# FPGA_Bank_0_CFG.net
KiCad netlist of a schematic drawn in Altium Designer
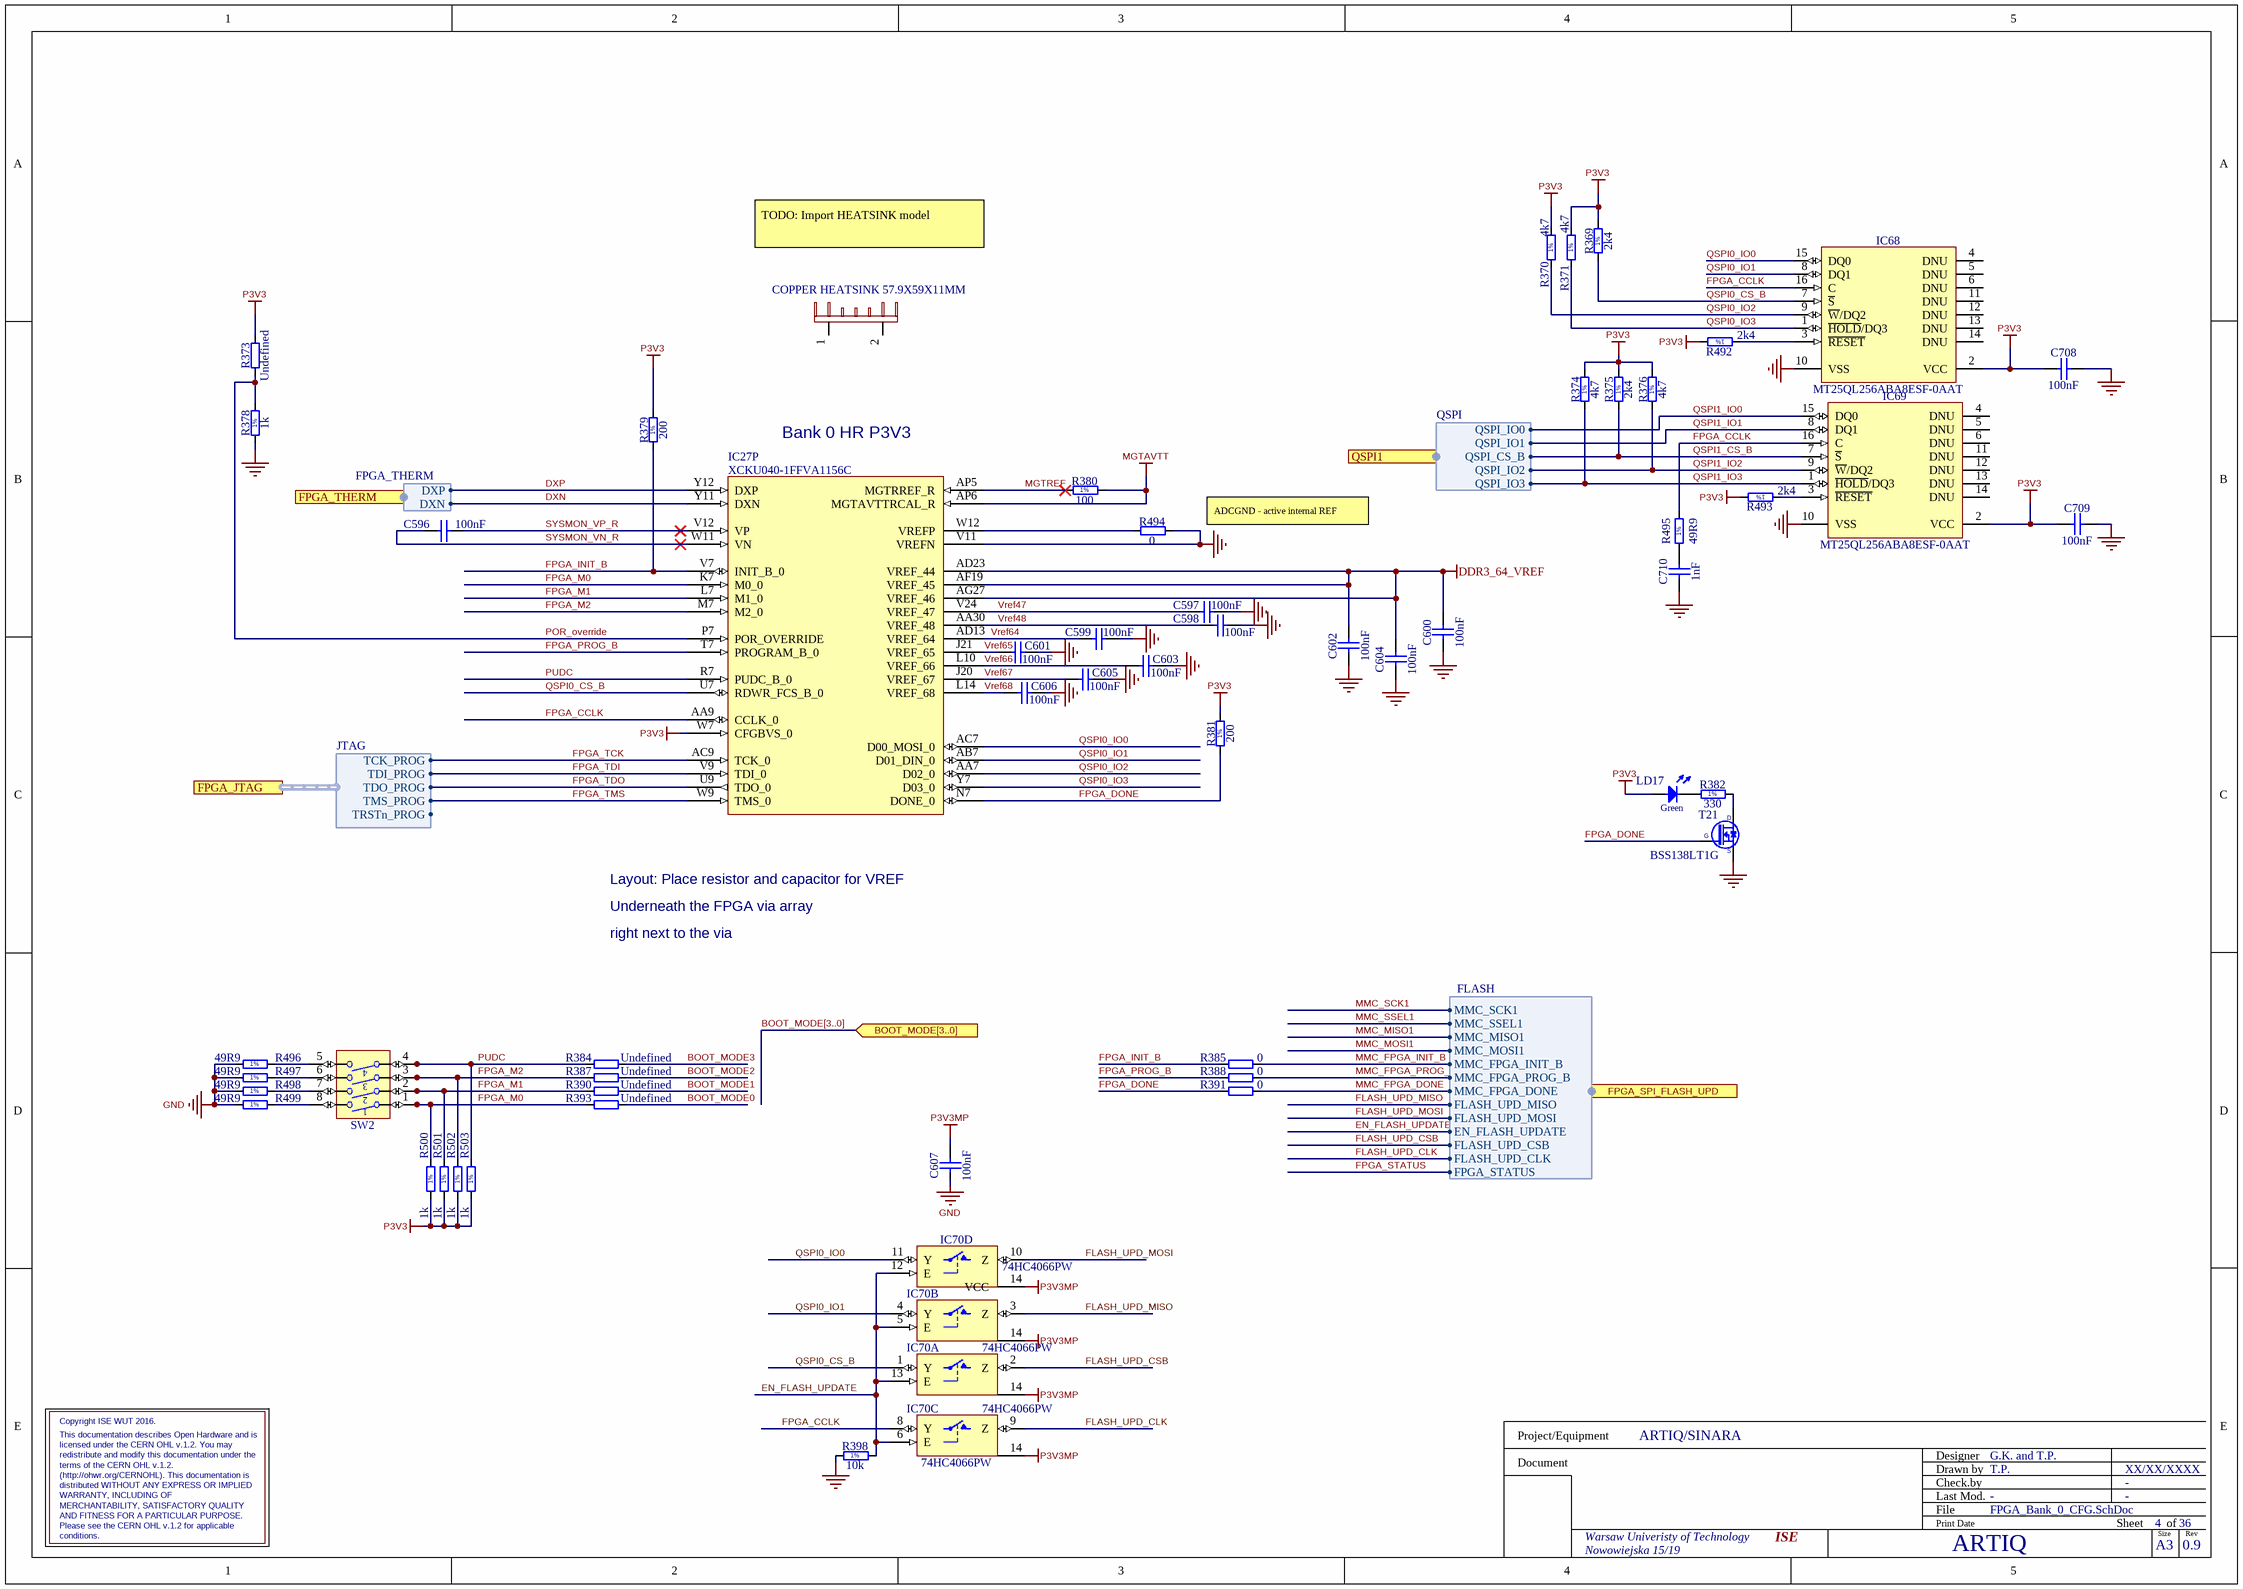
[diagram p0: FPGA_Bank_0_CFG.SchDoc]

(export (version "E")
  (design (tool "Eeschema 10.0.6"))
  (components
    (comp (ref "C596")
      (value "100nF")
      (footprint "CAPC0603X33N")
      (description "Non-polarised capacitor")
      (fields
        (field (name "MANUFACTURER PART NUMBER") "CC0201_100NF_6.3V_10%_X5R")
        (field (name "MANUFACTURER") "GENERIC")
        (field (name "AUTHOR") "CERN DEM JLC")
      )
      (libsource (lib "Capacitors") (part "Capacitor - non polarized"))
    )
    (comp (ref "C597")
      (value "100nF")
      (footprint "CAPC0603X33N")
      (description "Non-polarised capacitor")
      (fields
        (field (name "MANUFACTURER PART NUMBER") "CC0201_100NF_6.3V_10%_X5R")
        (field (name "MANUFACTURER") "GENERIC")
        (field (name "AUTHOR") "CERN DEM JLC")
      )
      (libsource (lib "Capacitors") (part "Capacitor - non polarized"))
    )
    (comp (ref "C598")
      (value "100nF")
      (footprint "CAPC0603X33N")
      (description "Non-polarised capacitor")
      (fields
        (field (name "MANUFACTURER PART NUMBER") "CC0201_100NF_6.3V_10%_X5R")
        (field (name "MANUFACTURER") "GENERIC")
        (field (name "AUTHOR") "CERN DEM JLC")
      )
      (libsource (lib "Capacitors") (part "Capacitor - non polarized"))
    )
    (comp (ref "C599")
      (value "100nF")
      (footprint "CAPC0603X33N")
      (description "Non-polarised capacitor")
      (fields
        (field (name "MANUFACTURER PART NUMBER") "CC0201_100NF_6.3V_10%_X5R")
        (field (name "MANUFACTURER") "GENERIC")
        (field (name "AUTHOR") "CERN DEM JLC")
      )
      (libsource (lib "Capacitors") (part "Capacitor - non polarized"))
    )
    (comp (ref "C600")
      (value "100nF")
      (footprint "CAPC0603X33N")
      (description "Non-polarised capacitor")
      (fields
        (field (name "MANUFACTURER PART NUMBER") "CC0201_100NF_6.3V_10%_X5R")
        (field (name "MANUFACTURER") "GENERIC")
        (field (name "AUTHOR") "CERN DEM JLC")
      )
      (libsource (lib "Capacitors") (part "Capacitor - non polarized"))
    )
    (comp (ref "C601")
      (value "100nF")
      (footprint "CAPC0603X33N")
      (description "Non-polarised capacitor")
      (fields
        (field (name "MANUFACTURER PART NUMBER") "CC0201_100NF_6.3V_10%_X5R")
        (field (name "MANUFACTURER") "GENERIC")
        (field (name "AUTHOR") "CERN DEM JLC")
      )
      (libsource (lib "Capacitors") (part "Capacitor - non polarized"))
    )
    (comp (ref "C602")
      (value "100nF")
      (footprint "CAPC0603X33N")
      (description "Non-polarised capacitor")
      (fields
        (field (name "MANUFACTURER PART NUMBER") "CC0201_100NF_6.3V_10%_X5R")
        (field (name "MANUFACTURER") "GENERIC")
        (field (name "AUTHOR") "CERN DEM JLC")
      )
      (libsource (lib "Capacitors") (part "Capacitor - non polarized"))
    )
    (comp (ref "C603")
      (value "100nF")
      (footprint "CAPC0603X33N")
      (description "Non-polarised capacitor")
      (fields
        (field (name "MANUFACTURER PART NUMBER") "CC0201_100NF_6.3V_10%_X5R")
        (field (name "MANUFACTURER") "GENERIC")
        (field (name "AUTHOR") "CERN DEM JLC")
      )
      (libsource (lib "Capacitors") (part "Capacitor - non polarized"))
    )
    (comp (ref "C604")
      (value "100nF")
      (footprint "CAPC0603X33N")
      (description "Non-polarised capacitor")
      (fields
        (field (name "MANUFACTURER PART NUMBER") "CC0201_100NF_6.3V_10%_X5R")
        (field (name "MANUFACTURER") "GENERIC")
        (field (name "AUTHOR") "CERN DEM JLC")
      )
      (libsource (lib "Capacitors") (part "Capacitor - non polarized"))
    )
    (comp (ref "C605")
      (value "100nF")
      (footprint "CAPC0603X33N")
      (description "Non-polarised capacitor")
      (fields
        (field (name "MANUFACTURER PART NUMBER") "CC0201_100NF_6.3V_10%_X5R")
        (field (name "MANUFACTURER") "GENERIC")
        (field (name "AUTHOR") "CERN DEM JLC")
      )
      (libsource (lib "Capacitors") (part "Capacitor - non polarized"))
    )
    (comp (ref "C606")
      (value "100nF")
      (footprint "CAPC0603X33N")
      (description "Non-polarised capacitor")
      (fields
        (field (name "MANUFACTURER PART NUMBER") "CC0201_100NF_6.3V_10%_X5R")
        (field (name "MANUFACTURER") "GENERIC")
        (field (name "AUTHOR") "CERN DEM JLC")
      )
      (libsource (lib "Capacitors") (part "Capacitor - non polarized"))
    )
    (comp (ref "C607")
      (value "100nF")
      (footprint "CAPC0603X33N")
      (description "Non-polarised capacitor")
      (fields
        (field (name "MANUFACTURER PART NUMBER") "CC0201_100NF_6.3V_10%_X5R")
        (field (name "MANUFACTURER") "GENERIC")
        (field (name "AUTHOR") "CERN DEM JLC")
      )
      (libsource (lib "Capacitors") (part "Capacitor - non polarized"))
    )
    (comp (ref "C708")
      (value "100nF")
      (footprint "CAPC0603X33N")
      (description "Non-polarised capacitor")
      (fields
        (field (name "MANUFACTURER PART NUMBER") "CC0201_100NF_6.3V_10%_X5R")
        (field (name "MANUFACTURER") "GENERIC")
        (field (name "AUTHOR") "CERN DEM JLC")
      )
      (libsource (lib "Capacitors") (part "Capacitor - non polarized"))
    )
    (comp (ref "C709")
      (value "100nF")
      (footprint "CAPC0603X33N")
      (description "Non-polarised capacitor")
      (fields
        (field (name "MANUFACTURER PART NUMBER") "CC0201_100NF_6.3V_10%_X5R")
        (field (name "MANUFACTURER") "GENERIC")
        (field (name "AUTHOR") "CERN DEM JLC")
      )
      (libsource (lib "Capacitors") (part "Capacitor - non polarized"))
    )
    (comp (ref "C710")
      (value "1nF")
      (footprint "CAPC1005X55N")
      (description "Non-polarised capacitor")
      (fields
        (field (name "MANUFACTURER PART NUMBER") "CC0402_1NF_50V_10%_X7R")
        (field (name "MANUFACTURER") "GENERIC")
        (field (name "AUTHOR") "CERN DEM JLC")
      )
      (libsource (lib "Capacitors") (part "Capacitor - non polarized"))
    )
    (comp (ref "HS1")
      (value "1.9K/W")
      (fields
        (field (name "MANUFACTURER PART NUMBER") "342947")
        (field (name "MANUFACTURER") "Aavid Thermalloy")
        (field (name "PART DESCRIPTION") "COPPER HEATSINK 57.9X59X11MM")
        (field (name "PART NUMBER") "HSINK_AAVID_342947")
      )
      (libsource (lib "altium-import") (part "root_0__Eletro-mechanical.DbLib"))
    )
    (comp (ref "IC27")
      (value "XCKU040-1FFVA1156C")
      (footprint "BGA1156C100P34X34_3500X3500X350")
      (description "Kintex UltraScale FPGA, 520 I/O, 530K Cells, 1156-Ball BGA, Speed Grade 1, Commercial Grade")
      (fields (field (name "MANUFACTURER") "XILINX") (field (name "AUTHOR") "CERN DEM CA"))
      (libsource (lib "ICs And Semiconductors") (part "XCKU040-1FFVA1156C"))
    )
    (comp (ref "IC68")
      (value "MT25QL256ABA8ESF-0AAT")
      (footprint "SOIC127P1030X265-16N")
      (description "256Mbit (32MB), 2.7V-3.6V, Multiple I/O Serial NOR Flash Memory,with Reset# & Hold#")
      (fields (field (name "MANUFACTURER") "MICRON TECHNOLOGY") (field (name "AUTHOR") "CERN DEM JLC"))
      (libsource (lib "ICs And Semiconductors") (part "MT25QL256ABA8ESF"))
    )
    (comp (ref "IC69")
      (value "MT25QL256ABA8ESF-0AAT")
      (footprint "SOIC127P1030X265-16N")
      (description "256Mbit (32MB), 2.7V-3.6V, Multiple I/O Serial NOR Flash Memory,with Reset# & Hold#")
      (fields (field (name "MANUFACTURER") "MICRON TECHNOLOGY") (field (name "AUTHOR") "CERN DEM JLC"))
      (libsource (lib "ICs And Semiconductors") (part "MT25QL256ABA8ESF"))
    )
    (comp (ref "IC70")
      (value "74HC4066PW")
      (footprint "SOP65P640X110-14N")
      (fields (field (name "MANUFACTURER") "NXP SEMICONDUCTORS") (field (name "AUTHOR") "CERN DEM JLC"))
      (libsource (lib "ICs And Semiconductors") (part "4066"))
    )
    (comp (ref "LD17")
      (value "Green")
      (footprint "LED_AVAGO_HSME-C120")
      (description "LED Green 1C 2A")
      (fields
        (field (name "MANUFACTURER PART NUMBER") "HSME-C120")
        (field (name "MANUFACTURER") "AVAGO TECHNOLOGIES")
        (field (name "AUTHOR") "CERN DEM JMW")
      )
      (libsource (lib "ICs And Semiconductors") (part "LED Green 1C 2A"))
    )
    (comp (ref "R369")
      (value "2k4")
      (footprint "RESC1005X40N")
      (description "Resistor - 1%")
      (fields
        (field (name "MANUFACTURER PART NUMBER") "R0402_2K4_1%_0.0625W_100PPM")
        (field (name "MANUFACTURER") "GENERIC")
        (field (name "AUTHOR") "CERN DEM JLC")
      )
      (libsource (lib "Resistors") (part "Resistor - 1%"))
    )
    (comp (ref "R370")
      (value "4k7")
      (footprint "RESC1005X40N")
      (description "Resistor - 1%")
      (fields
        (field (name "MANUFACTURER PART NUMBER") "R0402_4K7_1%_0.0625W_100PPM")
        (field (name "MANUFACTURER") "GENERIC")
        (field (name "AUTHOR") "CERN DEM JLC")
      )
      (libsource (lib "Resistors") (part "Resistor - 1%"))
    )
    (comp (ref "R371")
      (value "4k7")
      (footprint "RESC1005X40N")
      (description "Resistor - 1%")
      (fields
        (field (name "MANUFACTURER PART NUMBER") "R0402_4K7_1%_0.0625W_100PPM")
        (field (name "MANUFACTURER") "GENERIC")
        (field (name "AUTHOR") "CERN DEM JLC")
      )
      (libsource (lib "Resistors") (part "Resistor - 1%"))
    )
    (comp (ref "R373")
      (value "Undefined")
      (footprint "RESC1005X40N")
      (description "Resistor")
      (fields
        (field (name "MANUFACTURER PART NUMBER") "R0402_NO-VALUE")
        (field (name "AUTHOR") "CERN DEM JLC")
      )
      (libsource (lib "Resistors") (part "Resistor"))
    )
    (comp (ref "R374")
      (value "4k7")
      (footprint "RESC1005X40N")
      (description "Resistor - 1%")
      (fields
        (field (name "MANUFACTURER PART NUMBER") "R0402_4K7_1%_0.0625W_100PPM")
        (field (name "MANUFACTURER") "GENERIC")
        (field (name "AUTHOR") "CERN DEM JLC")
      )
      (libsource (lib "Resistors") (part "Resistor - 1%"))
    )
    (comp (ref "R375")
      (value "2k4")
      (footprint "RESC1005X40N")
      (description "Resistor - 1%")
      (fields
        (field (name "MANUFACTURER PART NUMBER") "R0402_2K4_1%_0.0625W_100PPM")
        (field (name "MANUFACTURER") "GENERIC")
        (field (name "AUTHOR") "CERN DEM JLC")
      )
      (libsource (lib "Resistors") (part "Resistor - 1%"))
    )
    (comp (ref "R376")
      (value "4k7")
      (footprint "RESC1005X40N")
      (description "Resistor - 1%")
      (fields
        (field (name "MANUFACTURER PART NUMBER") "R0402_4K7_1%_0.0625W_100PPM")
        (field (name "MANUFACTURER") "GENERIC")
        (field (name "AUTHOR") "CERN DEM JLC")
      )
      (libsource (lib "Resistors") (part "Resistor - 1%"))
    )
    (comp (ref "R378")
      (value "1k")
      (footprint "RESC1005X40N")
      (description "Resistor - 1%")
      (fields
        (field (name "MANUFACTURER PART NUMBER") "R0402_1K_1%_0.0625W_100PPM")
        (field (name "MANUFACTURER") "GENERIC")
        (field (name "AUTHOR") "CERN DEM JLC")
      )
      (libsource (lib "Resistors") (part "Resistor - 1%"))
    )
    (comp (ref "R379")
      (value "200")
      (footprint "RESC1005X40N")
      (description "Resistor - 1%")
      (fields
        (field (name "MANUFACTURER PART NUMBER") "R0402_200R_1%_0.0625W_100PPM")
        (field (name "MANUFACTURER") "GENERIC")
        (field (name "AUTHOR") "CERN DEM JLC")
      )
      (libsource (lib "Resistors") (part "Resistor - 1%"))
    )
    (comp (ref "R380")
      (value "100")
      (footprint "RESC0603X28N")
      (description "Resistor - 1%")
      (fields
        (field (name "MANUFACTURER PART NUMBER") "R0201_100R_1%_0.05W_200PPM")
        (field (name "MANUFACTURER") "GENERIC")
        (field (name "AUTHOR") "CERN DEM JLC")
      )
      (libsource (lib "Resistors") (part "Resistor - 1%"))
    )
    (comp (ref "R381")
      (value "200")
      (footprint "RESC1005X40N")
      (description "Resistor - 1%")
      (fields
        (field (name "MANUFACTURER PART NUMBER") "R0402_200R_1%_0.0625W_100PPM")
        (field (name "MANUFACTURER") "GENERIC")
        (field (name "AUTHOR") "CERN DEM JLC")
      )
      (libsource (lib "Resistors") (part "Resistor - 1%"))
    )
    (comp (ref "R382")
      (value "330")
      (footprint "RESC1005X40N")
      (description "Resistor - 1%")
      (fields
        (field (name "MANUFACTURER PART NUMBER") "R0402_330R_1%_0.0625W_100PPM")
        (field (name "MANUFACTURER") "GENERIC")
        (field (name "AUTHOR") "CERN DEM JLC")
      )
      (libsource (lib "Resistors") (part "Resistor - 1%"))
    )
    (comp (ref "R384")
      (value "Undefined")
      (footprint "RESC1005X40N")
      (description "Resistor")
      (fields
        (field (name "MANUFACTURER PART NUMBER") "R0402_NO-VALUE")
        (field (name "AUTHOR") "CERN DEM JLC")
      )
      (libsource (lib "Resistors") (part "Resistor"))
    )
    (comp (ref "R385")
      (value "0")
      (footprint "RESC1005X40N")
      (description "Resistor")
      (fields
        (field (name "MANUFACTURER PART NUMBER") "R0402_0R_JUMPER")
        (field (name "MANUFACTURER") "GENERIC")
        (field (name "AUTHOR") "CERN DEM JLC")
      )
      (libsource (lib "Resistors") (part "Resistor"))
    )
    (comp (ref "R387")
      (value "Undefined")
      (footprint "RESC1005X40N")
      (description "Resistor")
      (fields
        (field (name "MANUFACTURER PART NUMBER") "R0402_NO-VALUE")
        (field (name "AUTHOR") "CERN DEM JLC")
      )
      (libsource (lib "Resistors") (part "Resistor"))
    )
    (comp (ref "R388")
      (value "0")
      (footprint "RESC1005X40N")
      (description "Resistor")
      (fields
        (field (name "MANUFACTURER PART NUMBER") "R0402_0R_JUMPER")
        (field (name "MANUFACTURER") "GENERIC")
        (field (name "AUTHOR") "CERN DEM JLC")
      )
      (libsource (lib "Resistors") (part "Resistor"))
    )
    (comp (ref "R390")
      (value "Undefined")
      (footprint "RESC1005X40N")
      (description "Resistor")
      (fields
        (field (name "MANUFACTURER PART NUMBER") "R0402_NO-VALUE")
        (field (name "AUTHOR") "CERN DEM JLC")
      )
      (libsource (lib "Resistors") (part "Resistor"))
    )
    (comp (ref "R391")
      (value "0")
      (footprint "RESC1005X40N")
      (description "Resistor")
      (fields
        (field (name "MANUFACTURER PART NUMBER") "R0402_0R_JUMPER")
        (field (name "MANUFACTURER") "GENERIC")
        (field (name "AUTHOR") "CERN DEM JLC")
      )
      (libsource (lib "Resistors") (part "Resistor"))
    )
    (comp (ref "R393")
      (value "Undefined")
      (footprint "RESC1005X40N")
      (description "Resistor")
      (fields
        (field (name "MANUFACTURER PART NUMBER") "R0402_NO-VALUE")
        (field (name "AUTHOR") "CERN DEM JLC")
      )
      (libsource (lib "Resistors") (part "Resistor"))
    )
    (comp (ref "R398")
      (value "10k")
      (footprint "RESC1005X40N")
      (description "Resistor - 1%")
      (fields
        (field (name "MANUFACTURER PART NUMBER") "R0402_10K_1%_0.0625W_100PPM")
        (field (name "MANUFACTURER") "GENERIC")
        (field (name "AUTHOR") "CERN DEM JLC")
      )
      (libsource (lib "Resistors") (part "Resistor - 1%"))
    )
    (comp (ref "R492")
      (value "2k4")
      (footprint "RESC1005X40N")
      (description "Resistor - 1%")
      (fields
        (field (name "MANUFACTURER PART NUMBER") "R0402_2K4_1%_0.0625W_100PPM")
        (field (name "MANUFACTURER") "GENERIC")
        (field (name "AUTHOR") "CERN DEM JLC")
      )
      (libsource (lib "Resistors") (part "Resistor - 1%"))
    )
    (comp (ref "R493")
      (value "2k4")
      (footprint "RESC1005X40N")
      (description "Resistor - 1%")
      (fields
        (field (name "MANUFACTURER PART NUMBER") "R0402_2K4_1%_0.0625W_100PPM")
        (field (name "MANUFACTURER") "GENERIC")
        (field (name "AUTHOR") "CERN DEM JLC")
      )
      (libsource (lib "Resistors") (part "Resistor - 1%"))
    )
    (comp (ref "R494")
      (value "0")
      (footprint "RESC1005X40N")
      (description "Resistor")
      (fields
        (field (name "MANUFACTURER PART NUMBER") "R0402_0R_JUMPER")
        (field (name "MANUFACTURER") "GENERIC")
        (field (name "AUTHOR") "CERN DEM JLC")
      )
      (libsource (lib "Resistors") (part "Resistor"))
    )
    (comp (ref "R495")
      (value "49R9")
      (footprint "RESC1005X40N")
      (description "Resistor - 1%")
      (fields
        (field (name "MANUFACTURER PART NUMBER") "R0402_49R9_1%_0.0625W_100PPM")
        (field (name "MANUFACTURER") "GENERIC")
        (field (name "AUTHOR") "CERN DEM JLC")
      )
      (libsource (lib "Resistors") (part "Resistor - 1%"))
    )
    (comp (ref "R496")
      (value "49R9")
      (footprint "RESC1005X40N")
      (description "Resistor - 1%")
      (fields
        (field (name "MANUFACTURER PART NUMBER") "R0402_49R9_1%_0.0625W_100PPM")
        (field (name "MANUFACTURER") "GENERIC")
        (field (name "AUTHOR") "CERN DEM JLC")
      )
      (libsource (lib "Resistors") (part "Resistor - 1%"))
    )
    (comp (ref "R497")
      (value "49R9")
      (footprint "RESC1005X40N")
      (description "Resistor - 1%")
      (fields
        (field (name "MANUFACTURER PART NUMBER") "R0402_49R9_1%_0.0625W_100PPM")
        (field (name "MANUFACTURER") "GENERIC")
        (field (name "AUTHOR") "CERN DEM JLC")
      )
      (libsource (lib "Resistors") (part "Resistor - 1%"))
    )
    (comp (ref "R498")
      (value "49R9")
      (footprint "RESC1005X40N")
      (description "Resistor - 1%")
      (fields
        (field (name "MANUFACTURER PART NUMBER") "R0402_49R9_1%_0.0625W_100PPM")
        (field (name "MANUFACTURER") "GENERIC")
        (field (name "AUTHOR") "CERN DEM JLC")
      )
      (libsource (lib "Resistors") (part "Resistor - 1%"))
    )
    (comp (ref "R499")
      (value "49R9")
      (footprint "RESC1005X40N")
      (description "Resistor - 1%")
      (fields
        (field (name "MANUFACTURER PART NUMBER") "R0402_49R9_1%_0.0625W_100PPM")
        (field (name "MANUFACTURER") "GENERIC")
        (field (name "AUTHOR") "CERN DEM JLC")
      )
      (libsource (lib "Resistors") (part "Resistor - 1%"))
    )
    (comp (ref "R500")
      (value "1k")
      (footprint "RESC1005X40N")
      (description "Resistor - 1%")
      (fields
        (field (name "MANUFACTURER PART NUMBER") "R0402_1K_1%_0.0625W_100PPM")
        (field (name "MANUFACTURER") "GENERIC")
        (field (name "AUTHOR") "CERN DEM JLC")
      )
      (libsource (lib "Resistors") (part "Resistor - 1%"))
    )
    (comp (ref "R501")
      (value "1k")
      (footprint "RESC1005X40N")
      (description "Resistor - 1%")
      (fields
        (field (name "MANUFACTURER PART NUMBER") "R0402_1K_1%_0.0625W_100PPM")
        (field (name "MANUFACTURER") "GENERIC")
        (field (name "AUTHOR") "CERN DEM JLC")
      )
      (libsource (lib "Resistors") (part "Resistor - 1%"))
    )
    (comp (ref "R502")
      (value "1k")
      (footprint "RESC1005X40N")
      (description "Resistor - 1%")
      (fields
        (field (name "MANUFACTURER PART NUMBER") "R0402_1K_1%_0.0625W_100PPM")
        (field (name "MANUFACTURER") "GENERIC")
        (field (name "AUTHOR") "CERN DEM JLC")
      )
      (libsource (lib "Resistors") (part "Resistor - 1%"))
    )
    (comp (ref "R503")
      (value "1k")
      (footprint "RESC1005X40N")
      (description "Resistor - 1%")
      (fields
        (field (name "MANUFACTURER PART NUMBER") "R0402_1K_1%_0.0625W_100PPM")
        (field (name "MANUFACTURER") "GENERIC")
        (field (name "AUTHOR") "CERN DEM JLC")
      )
      (libsource (lib "Resistors") (part "Resistor - 1%"))
    )
    (comp (ref "SW2")
      (value "Switch")
      (footprint "SW_TYCO_1571983-4")
      (description "4 Ways SPST DIP Switch")
      (fields
        (field (name "MANUFACTURER PART NUMBER") "1571983-4 or GDH04S04")
        (field (name "MANUFACTURER") "TYCO")
        (field (name "AUTHOR") "CERN DEM JLC")
      )
      (libsource (lib "Eletro-mechanical") (part "SW 4x SPST DIP Switch"))
    )
    (comp (ref "T21")
      (value "BSS138LT1G")
      (footprint "SOT95P240X110-3N")
      (description "N-CHANNEL MOSFET WITH DIODE")
      (fields (field (name "MANUFACTURER") "ON SEMICONDUCTOR") (field (name "AUTHOR") "CERN DEM JLC"))
      (libsource (lib "ICs And Semiconductors") (part "N-MOSFET-D 1G 2S 3D"))
    )
  )
  (nets
    (net (code "5") (name "/BOOT_MODE0") (class "Default")
      (node (ref "R393") (pin "2") (pinfunction "2_2") (pintype "passive"))
    )
    (net (code "6") (name "/BOOT_MODE1") (class "Default")
      (node (ref "R390") (pin "2") (pinfunction "2_2") (pintype "passive"))
    )
    (net (code "7") (name "/BOOT_MODE2") (class "Default")
      (node (ref "R387") (pin "2") (pinfunction "2_2") (pintype "passive"))
    )
    (net (code "8") (name "/BOOT_MODE3") (class "Default")
      (node (ref "R384") (pin "2") (pinfunction "2_2") (pintype "passive"))
    )
    (net (code "10") (name "/DXN") (class "Default")
      (node (ref "IC27") (pin "Y11") (pinfunction "DXN_Y11") (pintype "input"))
    )
    (net (code "11") (name "/DXP") (class "Default")
      (node (ref "IC27") (pin "Y12") (pinfunction "DXP_Y12") (pintype "input"))
    )
    (net (code "12") (name "/EN_FLASH_UPDATE") (class "Default")
      (node (ref "IC70") (pin "12") (pinfunction "E_12") (pintype "input"))
      (node (ref "IC70") (pin "13") (pinfunction "E_13") (pintype "input"))
      (node (ref "IC70") (pin "5") (pinfunction "E_5") (pintype "input"))
      (node (ref "IC70") (pin "6") (pinfunction "E_6") (pintype "input"))
      (node (ref "R398") (pin "2") (pinfunction "2_2") (pintype "passive"))
    )
    (net (code "13") (name "/FLASH_UPD_CLK") (class "Default")
      (node (ref "IC70") (pin "9") (pinfunction "Z_9") (pintype "bidirectional"))
    )
    (net (code "14") (name "/FLASH_UPD_CSB") (class "Default")
      (node (ref "IC70") (pin "2") (pinfunction "Z_2") (pintype "bidirectional"))
    )
    (net (code "15") (name "/FLASH_UPD_MISO") (class "Default")
      (node (ref "IC70") (pin "3") (pinfunction "Z_3") (pintype "bidirectional"))
    )
    (net (code "16") (name "/FLASH_UPD_MOSI") (class "Default")
      (node (ref "IC70") (pin "10") (pinfunction "Z_10") (pintype "bidirectional"))
    )
    (net (code "17") (name "/FPGA_CCLK") (class "Default")
      (node (ref "IC27") (pin "AA9") (pinfunction "CCLK_0_AA9") (pintype "bidirectional"))
      (node (ref "IC68") (pin "16") (pinfunction "C_16") (pintype "input"))
      (node (ref "IC69") (pin "16") (pinfunction "C_16") (pintype "input"))
      (node (ref "IC70") (pin "8") (pinfunction "Y_8") (pintype "bidirectional"))
      (node (ref "R495") (pin "2") (pinfunction "2_2") (pintype "passive"))
    )
    (net (code "18") (name "/FPGA_DONE") (class "Default")
      (node (ref "IC27") (pin "N7") (pinfunction "DONE_0_N7") (pintype "bidirectional"))
      (node (ref "R381") (pin "1") (pinfunction "1_1") (pintype "passive"))
      (node (ref "R391") (pin "1") (pinfunction "1_1") (pintype "passive"))
      (node (ref "T21") (pin "1") (pinfunction "G_1") (pintype "passive"))
    )
    (net (code "19") (name "/FPGA_INIT_B") (class "Default")
      (node (ref "IC27") (pin "V7") (pinfunction "INIT_B_0_V7") (pintype "bidirectional"))
      (node (ref "R379") (pin "1") (pinfunction "1_1") (pintype "passive"))
      (node (ref "R385") (pin "1") (pinfunction "1_1") (pintype "passive"))
    )
    (net (code "20") (name "/FPGA_M0") (class "Default")
      (node (ref "IC27") (pin "K7") (pinfunction "M0_0_K7") (pintype "input"))
      (node (ref "R393") (pin "1") (pinfunction "1_1") (pintype "passive"))
      (node (ref "R500") (pin "2") (pinfunction "2_2") (pintype "passive"))
      (node (ref "SW2") (pin "1") (pinfunction "1_1") (pintype "bidirectional"))
    )
    (net (code "21") (name "/FPGA_M1") (class "Default")
      (node (ref "IC27") (pin "L7") (pinfunction "M1_0_L7") (pintype "input"))
      (node (ref "R390") (pin "1") (pinfunction "1_1") (pintype "passive"))
      (node (ref "R501") (pin "2") (pinfunction "2_2") (pintype "passive"))
      (node (ref "SW2") (pin "2") (pinfunction "2_2") (pintype "bidirectional"))
    )
    (net (code "22") (name "/FPGA_M2") (class "Default")
      (node (ref "IC27") (pin "M7") (pinfunction "M2_0_M7") (pintype "input"))
      (node (ref "R387") (pin "1") (pinfunction "1_1") (pintype "passive"))
      (node (ref "R502") (pin "2") (pinfunction "2_2") (pintype "passive"))
      (node (ref "SW2") (pin "3") (pinfunction "3_3") (pintype "bidirectional"))
    )
    (net (code "23") (name "/FPGA_PROG_B") (class "Default")
      (node (ref "IC27") (pin "T7") (pinfunction "PROGRAM_B_0_T7") (pintype "input"))
      (node (ref "R388") (pin "1") (pinfunction "1_1") (pintype "passive"))
    )
    (net (code "25") (name "/FPGA_TCK") (class "Default")
      (node (ref "IC27") (pin "AC9") (pinfunction "TCK_0_AC9") (pintype "input"))
    )
    (net (code "26") (name "/FPGA_TDI") (class "Default")
      (node (ref "IC27") (pin "V9") (pinfunction "TDI_0_V9") (pintype "input"))
    )
    (net (code "27") (name "/FPGA_TDO") (class "Default")
      (node (ref "IC27") (pin "U9") (pinfunction "TDO_0_U9") (pintype "output"))
    )
    (net (code "28") (name "/FPGA_TMS") (class "Default")
      (node (ref "IC27") (pin "W9") (pinfunction "TMS_0_W9") (pintype "input"))
    )
    (net (code "29") (name "/MGTREF") (class "Default")
      (node (ref "IC27") (pin "AP5") (pinfunction "MGTRREF_R_AP5") (pintype "input"))
      (node (ref "R380") (pin "1") (pinfunction "1_1") (pintype "passive"))
    )
    (net (code "30") (name "/MMC_FPGA_DONE") (class "Default")
      (node (ref "R391") (pin "2") (pinfunction "2_2") (pintype "passive"))
    )
    (net (code "31") (name "/MMC_FPGA_INIT_B") (class "Default")
      (node (ref "R385") (pin "2") (pinfunction "2_2") (pintype "passive"))
    )
    (net (code "32") (name "/MMC_FPGA_PROG_B") (class "Default")
      (node (ref "R388") (pin "2") (pinfunction "2_2") (pintype "passive"))
    )
    (net (code "37") (name "/POR_override") (class "Default")
      (node (ref "IC27") (pin "P7") (pinfunction "POR_OVERRIDE_P7") (pintype "input"))
      (node (ref "R373") (pin "1") (pinfunction "1_1") (pintype "passive"))
      (node (ref "R378") (pin "2") (pinfunction "2_2") (pintype "passive"))
    )
    (net (code "38") (name "/PUDC") (class "Default")
      (node (ref "IC27") (pin "R7") (pinfunction "PUDC_B_0_R7") (pintype "input"))
      (node (ref "R384") (pin "1") (pinfunction "1_1") (pintype "passive"))
      (node (ref "R503") (pin "2") (pinfunction "2_2") (pintype "passive"))
      (node (ref "SW2") (pin "4") (pinfunction "4_4") (pintype "bidirectional"))
    )
    (net (code "39") (name "/QSPI0_CS_B") (class "Default")
      (node (ref "IC27") (pin "U7") (pinfunction "RDWR_FCS_B_0_U7") (pintype "bidirectional"))
      (node (ref "IC68") (pin "7") (pinfunction "~{S}_7") (pintype "input"))
      (node (ref "IC70") (pin "1") (pinfunction "Y_1") (pintype "bidirectional"))
      (node (ref "R369") (pin "1") (pinfunction "1_1") (pintype "passive"))
    )
    (net (code "40") (name "/QSPI0_IO0") (class "Default")
      (node (ref "IC27") (pin "AC7") (pinfunction "D00_MOSI_0_AC7") (pintype "bidirectional"))
      (node (ref "IC68") (pin "15") (pinfunction "DQ0_15") (pintype "bidirectional"))
      (node (ref "IC70") (pin "11") (pinfunction "Y_11") (pintype "bidirectional"))
    )
    (net (code "41") (name "/QSPI0_IO1") (class "Default")
      (node (ref "IC27") (pin "AB7") (pinfunction "D01_DIN_0_AB7") (pintype "bidirectional"))
      (node (ref "IC68") (pin "8") (pinfunction "DQ1_8") (pintype "bidirectional"))
      (node (ref "IC70") (pin "4") (pinfunction "Y_4") (pintype "bidirectional"))
    )
    (net (code "42") (name "/QSPI0_IO2") (class "Default")
      (node (ref "IC27") (pin "AA7") (pinfunction "D02_0_AA7") (pintype "bidirectional"))
      (node (ref "IC68") (pin "9") (pinfunction "~{W}/DQ2_9") (pintype "bidirectional"))
      (node (ref "R370") (pin "1") (pinfunction "1_1") (pintype "passive"))
    )
    (net (code "43") (name "/QSPI0_IO3") (class "Default")
      (node (ref "IC27") (pin "Y7") (pinfunction "D03_0_Y7") (pintype "bidirectional"))
      (node (ref "IC68") (pin "1") (pinfunction "~{HOLD}/DQ3_1") (pintype "bidirectional"))
      (node (ref "R371") (pin "1") (pinfunction "1_1") (pintype "passive"))
    )
    (net (code "44") (name "/QSPI1_CS_B") (class "Default")
      (node (ref "IC69") (pin "7") (pinfunction "~{S}_7") (pintype "input"))
      (node (ref "R375") (pin "1") (pinfunction "1_1") (pintype "passive"))
    )
    (net (code "45") (name "/QSPI1_IO0") (class "Default")
      (node (ref "IC69") (pin "15") (pinfunction "DQ0_15") (pintype "bidirectional"))
    )
    (net (code "46") (name "/QSPI1_IO1") (class "Default")
      (node (ref "IC69") (pin "8") (pinfunction "DQ1_8") (pintype "bidirectional"))
    )
    (net (code "47") (name "/QSPI1_IO2") (class "Default")
      (node (ref "IC69") (pin "9") (pinfunction "~{W}/DQ2_9") (pintype "bidirectional"))
      (node (ref "R376") (pin "1") (pinfunction "1_1") (pintype "passive"))
    )
    (net (code "48") (name "/QSPI1_IO3") (class "Default")
      (node (ref "IC69") (pin "1") (pinfunction "~{HOLD}/DQ3_1") (pintype "bidirectional"))
      (node (ref "R374") (pin "1") (pinfunction "1_1") (pintype "passive"))
    )
    (net (code "49") (name "/SYSMON_VN_R") (class "Default")
      (node (ref "C596") (pin "1") (pinfunction "1_1") (pintype "passive"))
      (node (ref "IC27") (pin "W11") (pinfunction "VN_W11") (pintype "input"))
    )
    (net (code "50") (name "/SYSMON_VP_R") (class "Default")
      (node (ref "C596") (pin "2") (pinfunction "2_2") (pintype "passive"))
      (node (ref "IC27") (pin "V12") (pinfunction "VP_V12") (pintype "input"))
    )
    (net (code "51") (name "/Vref47") (class "Default")
      (node (ref "C597") (pin "1") (pinfunction "1_1") (pintype "passive"))
      (node (ref "IC27") (pin "V24") (pinfunction "VREF_47_V24") (pintype "power_in"))
    )
    (net (code "52") (name "/Vref48") (class "Default")
      (node (ref "C598") (pin "1") (pinfunction "1_1") (pintype "passive"))
      (node (ref "IC27") (pin "AA30") (pinfunction "VREF_48_AA30") (pintype "power_in"))
    )
    (net (code "53") (name "/Vref64") (class "Default")
      (node (ref "C599") (pin "1") (pinfunction "1_1") (pintype "passive"))
      (node (ref "IC27") (pin "AD13") (pinfunction "VREF_64_AD13") (pintype "power_in"))
    )
    (net (code "54") (name "/Vref65") (class "Default")
      (node (ref "C601") (pin "1") (pinfunction "1_1") (pintype "passive"))
      (node (ref "IC27") (pin "J21") (pinfunction "VREF_65_J21") (pintype "power_in"))
    )
    (net (code "55") (name "/Vref66") (class "Default")
      (node (ref "C603") (pin "1") (pinfunction "1_1") (pintype "passive"))
      (node (ref "IC27") (pin "L10") (pinfunction "VREF_66_L10") (pintype "power_in"))
    )
    (net (code "56") (name "/Vref67") (class "Default")
      (node (ref "C605") (pin "1") (pinfunction "1_1") (pintype "passive"))
      (node (ref "IC27") (pin "J20") (pinfunction "VREF_67_J20") (pintype "power_in"))
    )
    (net (code "57") (name "/Vref68") (class "Default")
      (node (ref "C606") (pin "1") (pinfunction "1_1") (pintype "passive"))
      (node (ref "IC27") (pin "L14") (pinfunction "VREF_68_L14") (pintype "power_in"))
    )
    (net (code "62") (name "DDR3_64_VREF") (class "Default")
      (node (ref "C600") (pin "1") (pinfunction "1_1") (pintype "passive"))
      (node (ref "C602") (pin "1") (pinfunction "1_1") (pintype "passive"))
      (node (ref "C604") (pin "1") (pinfunction "1_1") (pintype "passive"))
      (node (ref "IC27") (pin "AD23") (pinfunction "VREF_44_AD23") (pintype "power_in"))
      (node (ref "IC27") (pin "AF19") (pinfunction "VREF_45_AF19") (pintype "power_in"))
      (node (ref "IC27") (pin "AG27") (pinfunction "VREF_46_AG27") (pintype "power_in"))
    )
    (net (code "63") (name "GND") (class "Default")
      (node (ref "C597") (pin "2") (pinfunction "2_2") (pintype "passive"))
      (node (ref "C598") (pin "2") (pinfunction "2_2") (pintype "passive"))
      (node (ref "C599") (pin "2") (pinfunction "2_2") (pintype "passive"))
      (node (ref "C600") (pin "2") (pinfunction "2_2") (pintype "passive"))
      (node (ref "C601") (pin "2") (pinfunction "2_2") (pintype "passive"))
      (node (ref "C602") (pin "2") (pinfunction "2_2") (pintype "passive"))
      (node (ref "C603") (pin "2") (pinfunction "2_2") (pintype "passive"))
      (node (ref "C604") (pin "2") (pinfunction "2_2") (pintype "passive"))
      (node (ref "C605") (pin "2") (pinfunction "2_2") (pintype "passive"))
      (node (ref "C606") (pin "2") (pinfunction "2_2") (pintype "passive"))
      (node (ref "C607") (pin "1") (pinfunction "1_1") (pintype "passive"))
      (node (ref "C708") (pin "1") (pinfunction "1_1") (pintype "passive"))
      (node (ref "C709") (pin "1") (pinfunction "1_1") (pintype "passive"))
      (node (ref "C710") (pin "1") (pinfunction "1_1") (pintype "passive"))
      (node (ref "IC27") (pin "V11") (pinfunction "VREFN_V11") (pintype "power_in"))
      (node (ref "IC68") (pin "10") (pinfunction "VSS_10") (pintype "power_in"))
      (node (ref "IC69") (pin "10") (pinfunction "VSS_10") (pintype "power_in"))
      (node (ref "IC70") (pin "7") (pinfunction "GND_7") (pintype "power_in"))
      (node (ref "R378") (pin "1") (pinfunction "1_1") (pintype "passive"))
      (node (ref "R398") (pin "1") (pinfunction "1_1") (pintype "passive"))
      (node (ref "R494") (pin "2") (pinfunction "2_2") (pintype "passive"))
      (node (ref "R496") (pin "1") (pinfunction "1_1") (pintype "passive"))
      (node (ref "R497") (pin "1") (pinfunction "1_1") (pintype "passive"))
      (node (ref "R498") (pin "1") (pinfunction "1_1") (pintype "passive"))
      (node (ref "R499") (pin "1") (pinfunction "1_1") (pintype "passive"))
      (node (ref "T21") (pin "2") (pinfunction "S_2") (pintype "passive"))
    )
    (net (code "64") (name "MGTAVTT") (class "Default")
      (node (ref "IC27") (pin "AP6") (pinfunction "MGTAVTTRCAL_R_AP6") (pintype "input"))
      (node (ref "R380") (pin "2") (pinfunction "2_2") (pintype "passive"))
    )
    (net (code "65") (name "Net-(C710-Pad2)") (class "Default")
      (node (ref "C710") (pin "2") (pinfunction "2_2") (pintype "passive"))
      (node (ref "R495") (pin "1") (pinfunction "1_1") (pintype "passive"))
    )
    (net (code "66") (name "Net-(IC27P-VREFP)") (class "Default")
      (node (ref "IC27") (pin "W12") (pinfunction "VREFP_W12") (pintype "power_in"))
      (node (ref "R494") (pin "1") (pinfunction "1_1") (pintype "passive"))
    )
    (net (code "67") (name "Net-(IC68-~{RESET})") (class "Default")
      (node (ref "IC68") (pin "3") (pinfunction "~{RESET}_3") (pintype "input"))
      (node (ref "R492") (pin "1") (pinfunction "1_1") (pintype "passive"))
    )
    (net (code "68") (name "Net-(IC69-~{RESET})") (class "Default")
      (node (ref "IC69") (pin "3") (pinfunction "~{RESET}_3") (pintype "input"))
      (node (ref "R493") (pin "1") (pinfunction "1_1") (pintype "passive"))
    )
    (net (code "69") (name "Net-(LD17-C)") (class "Default")
      (node (ref "LD17") (pin "1") (pinfunction "C_1") (pintype "passive"))
      (node (ref "R382") (pin "1") (pinfunction "1_1") (pintype "passive"))
    )
    (net (code "70") (name "Net-(R496-Pad2)") (class "Default")
      (node (ref "R496") (pin "2") (pinfunction "2_2") (pintype "passive"))
      (node (ref "SW2") (pin "5") (pinfunction "5_5") (pintype "bidirectional"))
    )
    (net (code "71") (name "Net-(R497-Pad2)") (class "Default")
      (node (ref "R497") (pin "2") (pinfunction "2_2") (pintype "passive"))
      (node (ref "SW2") (pin "6") (pinfunction "6_6") (pintype "bidirectional"))
    )
    (net (code "72") (name "Net-(R498-Pad2)") (class "Default")
      (node (ref "R498") (pin "2") (pinfunction "2_2") (pintype "passive"))
      (node (ref "SW2") (pin "7") (pinfunction "7_7") (pintype "bidirectional"))
    )
    (net (code "73") (name "Net-(R499-Pad2)") (class "Default")
      (node (ref "R499") (pin "2") (pinfunction "2_2") (pintype "passive"))
      (node (ref "SW2") (pin "8") (pinfunction "8_8") (pintype "bidirectional"))
    )
    (net (code "74") (name "Net-(T21-D)") (class "Default")
      (node (ref "R382") (pin "2") (pinfunction "2_2") (pintype "passive"))
      (node (ref "T21") (pin "3") (pinfunction "D_3") (pintype "passive"))
    )
    (net (code "75") (name "P3V3") (class "Default")
      (node (ref "C708") (pin "2") (pinfunction "2_2") (pintype "passive"))
      (node (ref "C709") (pin "2") (pinfunction "2_2") (pintype "passive"))
      (node (ref "IC27") (pin "W7") (pinfunction "CFGBVS_0_W7") (pintype "input"))
      (node (ref "IC68") (pin "2") (pinfunction "VCC_2") (pintype "power_in"))
      (node (ref "IC69") (pin "2") (pinfunction "VCC_2") (pintype "power_in"))
      (node (ref "LD17") (pin "2") (pinfunction "A_2") (pintype "passive"))
      (node (ref "R369") (pin "2") (pinfunction "2_2") (pintype "passive"))
      (node (ref "R370") (pin "2") (pinfunction "2_2") (pintype "passive"))
      (node (ref "R371") (pin "2") (pinfunction "2_2") (pintype "passive"))
      (node (ref "R373") (pin "2") (pinfunction "2_2") (pintype "passive"))
      (node (ref "R374") (pin "2") (pinfunction "2_2") (pintype "passive"))
      (node (ref "R375") (pin "2") (pinfunction "2_2") (pintype "passive"))
      (node (ref "R376") (pin "2") (pinfunction "2_2") (pintype "passive"))
      (node (ref "R379") (pin "2") (pinfunction "2_2") (pintype "passive"))
      (node (ref "R381") (pin "2") (pinfunction "2_2") (pintype "passive"))
      (node (ref "R492") (pin "2") (pinfunction "2_2") (pintype "passive"))
      (node (ref "R493") (pin "2") (pinfunction "2_2") (pintype "passive"))
      (node (ref "R500") (pin "1") (pinfunction "1_1") (pintype "passive"))
      (node (ref "R501") (pin "1") (pinfunction "1_1") (pintype "passive"))
      (node (ref "R502") (pin "1") (pinfunction "1_1") (pintype "passive"))
      (node (ref "R503") (pin "1") (pinfunction "1_1") (pintype "passive"))
    )
    (net (code "76") (name "P3V3MP") (class "Default")
      (node (ref "C607") (pin "2") (pinfunction "2_2") (pintype "passive"))
      (node (ref "IC70") (pin "14") (pinfunction "VCC_14") (pintype "power_in"))
    )
    (net (code "77") (name "unconnected-(HS1-MOUNT1-Pad1)") (class "Default")
      (node (ref "HS1") (pin "1") (pinfunction "MOUNT1_1") (pintype "passive"))
    )
    (net (code "78") (name "unconnected-(HS1-MOUNT2-Pad2)") (class "Default")
      (node (ref "HS1") (pin "2") (pinfunction "MOUNT2_2") (pintype "passive"))
    )
    (net (code "79") (name "unconnected-(IC68-DNU-Pad4)") (class "Default")
      (node (ref "IC68") (pin "4") (pinfunction "DNU_4") (pintype "passive"))
    )
    (net (code "80") (name "unconnected-(IC68-DNU-Pad5)") (class "Default")
      (node (ref "IC68") (pin "5") (pinfunction "DNU_5") (pintype "passive"))
    )
    (net (code "81") (name "unconnected-(IC68-DNU-Pad6)") (class "Default")
      (node (ref "IC68") (pin "6") (pinfunction "DNU_6") (pintype "passive"))
    )
    (net (code "82") (name "unconnected-(IC68-DNU-Pad11)") (class "Default")
      (node (ref "IC68") (pin "11") (pinfunction "DNU_11") (pintype "passive"))
    )
    (net (code "83") (name "unconnected-(IC68-DNU-Pad12)") (class "Default")
      (node (ref "IC68") (pin "12") (pinfunction "DNU_12") (pintype "passive"))
    )
    (net (code "84") (name "unconnected-(IC68-DNU-Pad13)") (class "Default")
      (node (ref "IC68") (pin "13") (pinfunction "DNU_13") (pintype "passive"))
    )
    (net (code "85") (name "unconnected-(IC68-DNU-Pad14)") (class "Default")
      (node (ref "IC68") (pin "14") (pinfunction "DNU_14") (pintype "passive"))
    )
    (net (code "86") (name "unconnected-(IC69-DNU-Pad4)") (class "Default")
      (node (ref "IC69") (pin "4") (pinfunction "DNU_4") (pintype "passive"))
    )
    (net (code "87") (name "unconnected-(IC69-DNU-Pad5)") (class "Default")
      (node (ref "IC69") (pin "5") (pinfunction "DNU_5") (pintype "passive"))
    )
    (net (code "88") (name "unconnected-(IC69-DNU-Pad6)") (class "Default")
      (node (ref "IC69") (pin "6") (pinfunction "DNU_6") (pintype "passive"))
    )
    (net (code "89") (name "unconnected-(IC69-DNU-Pad11)") (class "Default")
      (node (ref "IC69") (pin "11") (pinfunction "DNU_11") (pintype "passive"))
    )
    (net (code "90") (name "unconnected-(IC69-DNU-Pad12)") (class "Default")
      (node (ref "IC69") (pin "12") (pinfunction "DNU_12") (pintype "passive"))
    )
    (net (code "91") (name "unconnected-(IC69-DNU-Pad13)") (class "Default")
      (node (ref "IC69") (pin "13") (pinfunction "DNU_13") (pintype "passive"))
    )
    (net (code "92") (name "unconnected-(IC69-DNU-Pad14)") (class "Default")
      (node (ref "IC69") (pin "14") (pinfunction "DNU_14") (pintype "passive"))
    )
  )
)
